# schema_v3_0.net
KiCad netlist of a schematic drawn in EAGLE
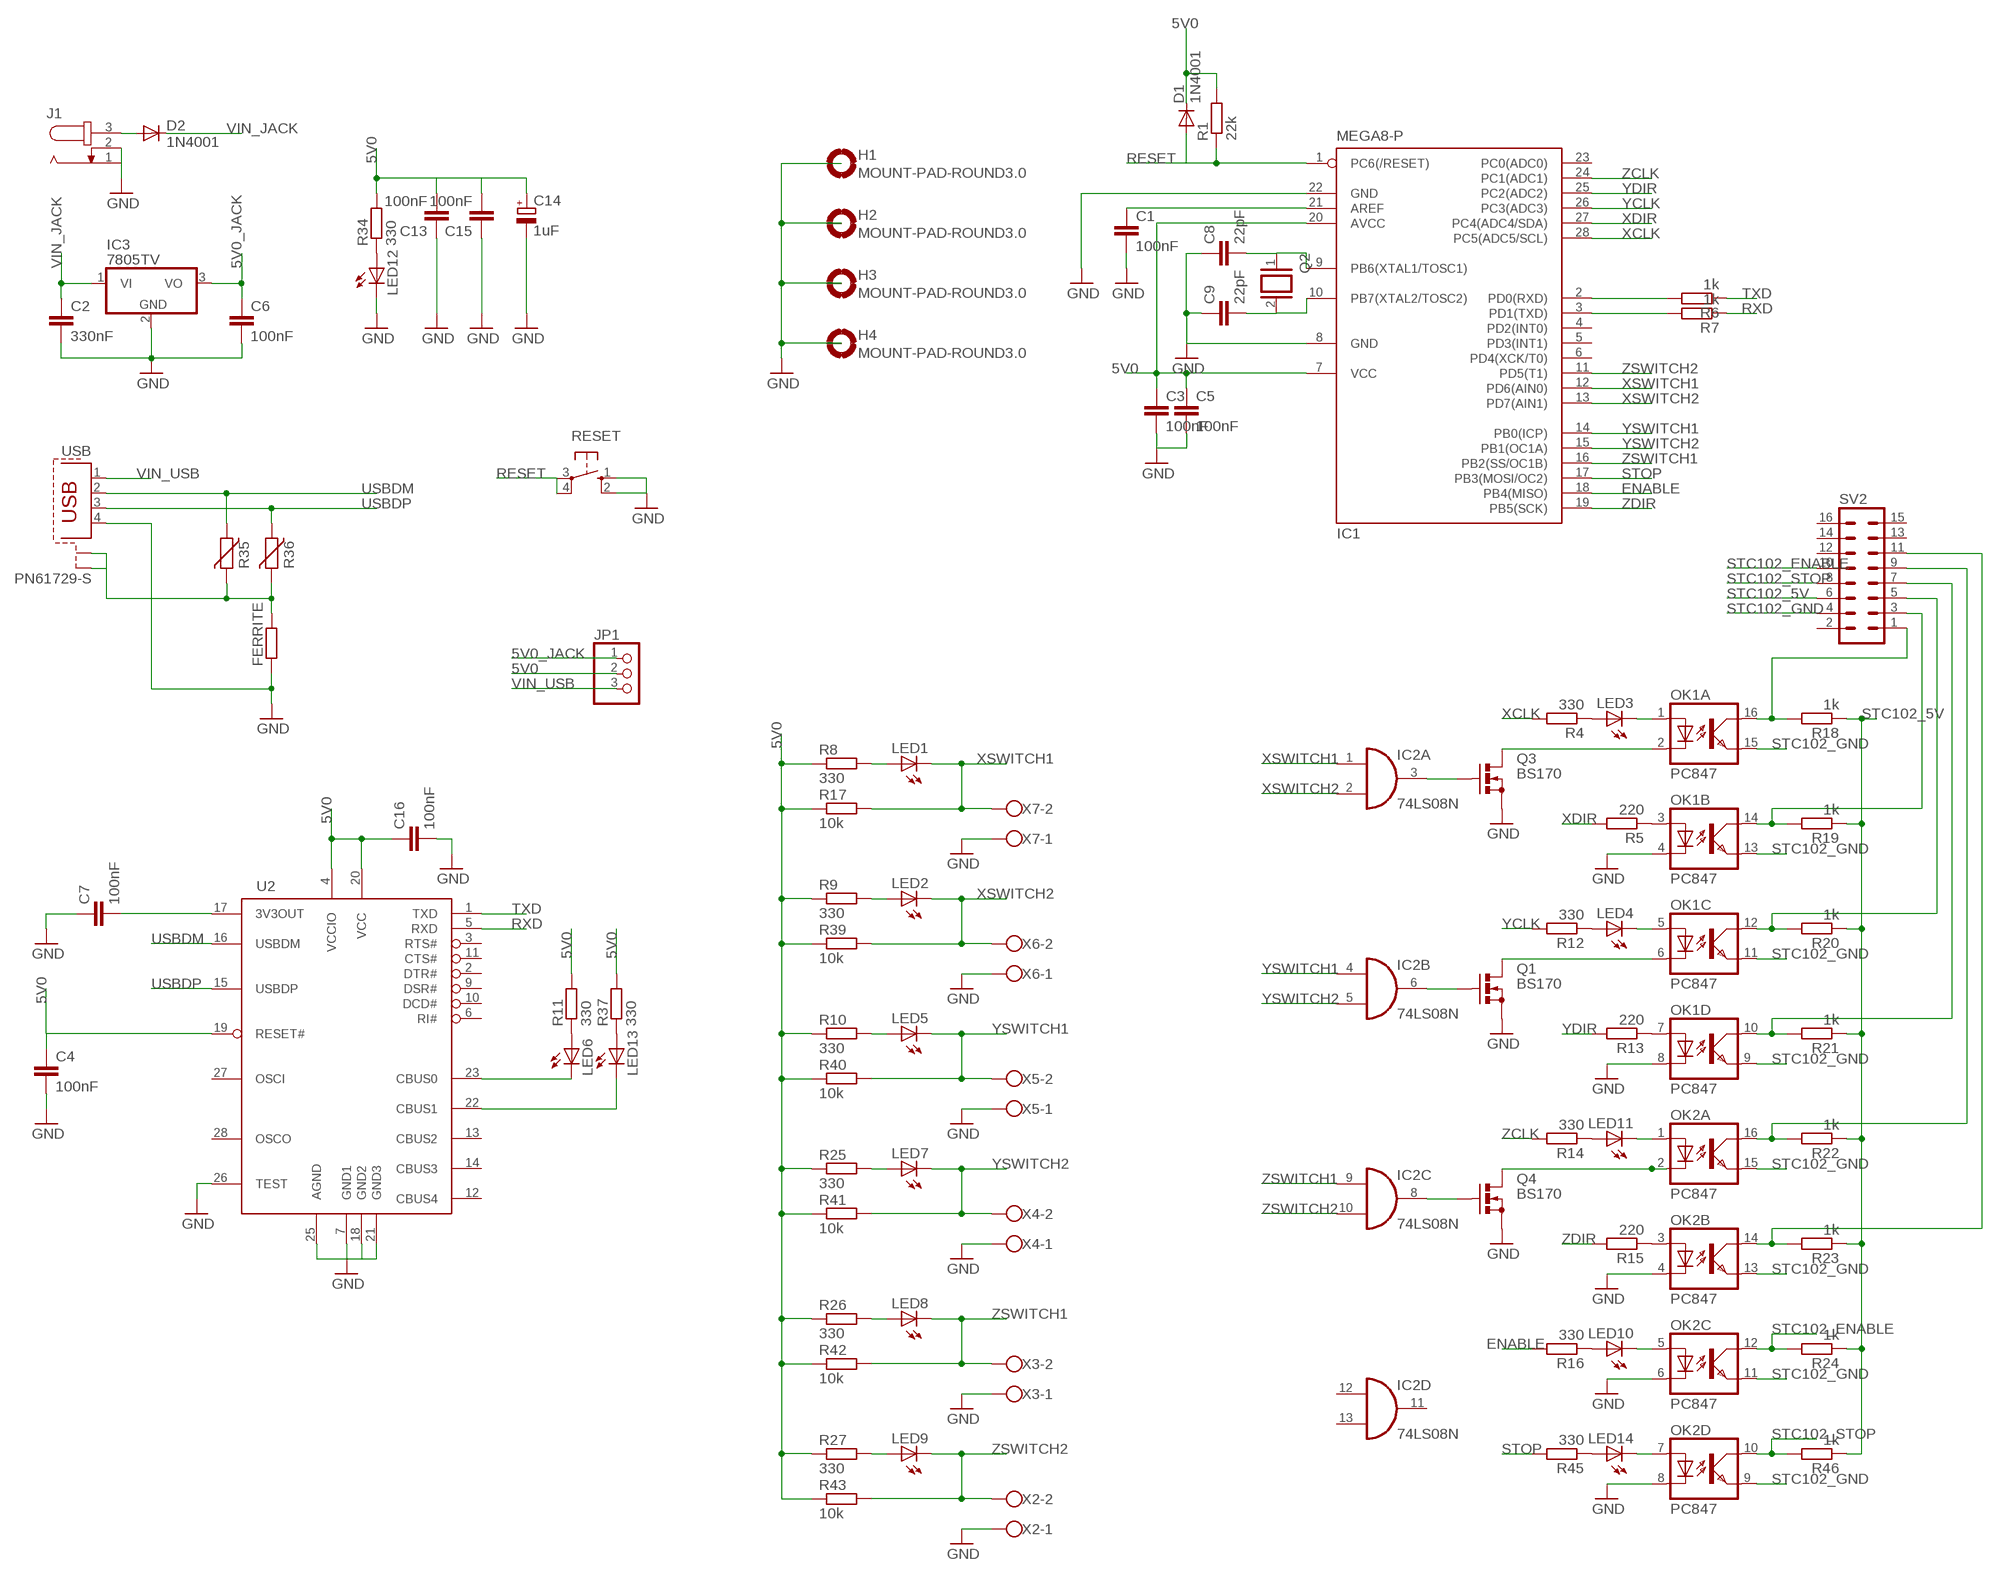
[diagram p0: schematic, sheet 1]

(export (version "E")
  (design (tool "Eeschema 10.0.6"))
  (components
    (comp (ref "C1")
      (value "100nF")
      (footprint "eagle-import:C0805")
      (libsource (lib "eagle-import") (part "C-EUC0805"))
    )
    (comp (ref "C2")
      (value "330nF")
      (footprint "eagle-import:C025-025X050")
      (libsource (lib "eagle-import") (part "C-EU025-025X050"))
    )
    (comp (ref "C3")
      (value "100nF")
      (footprint "eagle-import:C025-025X050")
      (libsource (lib "eagle-import") (part "C-EU025-025X050"))
    )
    (comp (ref "C4")
      (value "100nF")
      (footprint "eagle-import:C0603K")
      (libsource (lib "eagle-import") (part "C-EUC0603K"))
    )
    (comp (ref "C5")
      (value "100nF")
      (footprint "eagle-import:C025-025X050")
      (libsource (lib "eagle-import") (part "C-EU025-025X050"))
    )
    (comp (ref "C6")
      (value "100nF")
      (footprint "eagle-import:C025-025X050")
      (libsource (lib "eagle-import") (part "C-EU025-025X050"))
    )
    (comp (ref "C7")
      (value "100nF")
      (footprint "eagle-import:C0603K")
      (libsource (lib "eagle-import") (part "C-EUC0603K"))
    )
    (comp (ref "C8")
      (value "22pF")
      (footprint "eagle-import:C025-025X050")
      (libsource (lib "eagle-import") (part "C-EU025-025X050"))
    )
    (comp (ref "C9")
      (value "22pF")
      (footprint "eagle-import:C025-025X050")
      (libsource (lib "eagle-import") (part "C-EU025-025X050"))
    )
    (comp (ref "C13")
      (value "100nF")
      (footprint "eagle-import:C025-025X050")
      (libsource (lib "eagle-import") (part "C-EU025-025X050"))
    )
    (comp (ref "C14")
      (value "1uF")
      (footprint "eagle-import:E2,5-5")
      (libsource (lib "eagle-import") (part "CPOL-EUE2.5-5"))
    )
    (comp (ref "C15")
      (value "100nF")
      (footprint "eagle-import:C025-025X050")
      (libsource (lib "eagle-import") (part "C-EU025-025X050"))
    )
    (comp (ref "C16")
      (value "100nF")
      (footprint "eagle-import:C0603K")
      (libsource (lib "eagle-import") (part "C-EUC0603K"))
    )
    (comp (ref "D1")
      (value "1N4001")
      (footprint "eagle-import:DO41-10")
      (libsource (lib "eagle-import") (part "1N4004"))
    )
    (comp (ref "D2")
      (value "1N4001")
      (footprint "eagle-import:DO41-10")
      (libsource (lib "eagle-import") (part "1N4004"))
    )
    (comp (ref "FERRITE")
      (value "R-EU_M0805")
      (footprint "eagle-import:M0805")
      (libsource (lib "eagle-import") (part "resistor_R-EU_M0805"))
    )
    (comp (ref "H1")
      (value "MOUNT-PAD-ROUND3.0")
      (footprint "eagle-import:3,0-PAD")
      (libsource (lib "eagle-import") (part "MOUNT-PAD-ROUND3.0"))
    )
    (comp (ref "H2")
      (value "MOUNT-PAD-ROUND3.0")
      (footprint "eagle-import:3,0-PAD")
      (libsource (lib "eagle-import") (part "MOUNT-PAD-ROUND3.0"))
    )
    (comp (ref "H3")
      (value "MOUNT-PAD-ROUND3.0")
      (footprint "eagle-import:3,0-PAD")
      (libsource (lib "eagle-import") (part "MOUNT-PAD-ROUND3.0"))
    )
    (comp (ref "H4")
      (value "MOUNT-PAD-ROUND3.0")
      (footprint "eagle-import:3,0-PAD")
      (libsource (lib "eagle-import") (part "MOUNT-PAD-ROUND3.0"))
    )
    (comp (ref "IC1")
      (value "MEGA8-P")
      (footprint "eagle-import:DIL28-3")
      (libsource (lib "eagle-import") (part "MEGA8-P"))
    )
    (comp (ref "IC2")
      (value "74LS08N")
      (footprint "eagle-import:DIL14")
      (libsource (lib "eagle-import") (part "7408NLS"))
    )
    (comp (ref "IC3")
      (value "7805TV")
      (footprint "eagle-import:TO220V")
      (libsource (lib "eagle-import") (part "78TV05"))
    )
    (comp (ref "J1")
      (value "JACK-PLUG0")
      (footprint "eagle-import:SPC4077")
      (libsource (lib "eagle-import") (part "JACK-PLUG0"))
    )
    (comp (ref "JP1")
      (value "PINHD-1X3")
      (footprint "eagle-import:1X03")
      (libsource (lib "eagle-import") (part "PINHD-1X3"))
    )
    (comp (ref "LED1")
      (value "LED3MM")
      (footprint "eagle-import:LED3MM")
      (libsource (lib "eagle-import") (part "LED3MM"))
    )
    (comp (ref "LED2")
      (value "LED3MM")
      (footprint "eagle-import:LED3MM")
      (libsource (lib "eagle-import") (part "LED3MM"))
    )
    (comp (ref "LED3")
      (value "LED3MM")
      (footprint "eagle-import:LED3MM")
      (libsource (lib "eagle-import") (part "LED3MM"))
    )
    (comp (ref "LED4")
      (value "LED3MM")
      (footprint "eagle-import:LED3MM")
      (libsource (lib "eagle-import") (part "LED3MM"))
    )
    (comp (ref "LED5")
      (value "LED3MM")
      (footprint "eagle-import:LED3MM")
      (libsource (lib "eagle-import") (part "LED3MM"))
    )
    (comp (ref "LED6")
      (value "LED3MM")
      (footprint "eagle-import:LED3MM")
      (libsource (lib "eagle-import") (part "LED3MM"))
    )
    (comp (ref "LED7")
      (value "LED3MM")
      (footprint "eagle-import:LED3MM")
      (libsource (lib "eagle-import") (part "LED3MM"))
    )
    (comp (ref "LED8")
      (value "LED3MM")
      (footprint "eagle-import:LED3MM")
      (libsource (lib "eagle-import") (part "LED3MM"))
    )
    (comp (ref "LED9")
      (value "LED3MM")
      (footprint "eagle-import:LED3MM")
      (libsource (lib "eagle-import") (part "LED3MM"))
    )
    (comp (ref "LED10")
      (value "LED3MM")
      (footprint "eagle-import:LED3MM")
      (libsource (lib "eagle-import") (part "LED3MM"))
    )
    (comp (ref "LED11")
      (value "LED3MM")
      (footprint "eagle-import:LED3MM")
      (libsource (lib "eagle-import") (part "LED3MM"))
    )
    (comp (ref "LED12")
      (value "LED3MM")
      (footprint "eagle-import:LED3MM")
      (libsource (lib "eagle-import") (part "LED3MM"))
    )
    (comp (ref "LED13")
      (value "LED3MM")
      (footprint "eagle-import:LED3MM")
      (libsource (lib "eagle-import") (part "LED3MM"))
    )
    (comp (ref "LED14")
      (value "LED3MM")
      (footprint "eagle-import:LED3MM")
      (libsource (lib "eagle-import") (part "LED3MM"))
    )
    (comp (ref "OK1")
      (value "PC847")
      (footprint "eagle-import:DIL16")
      (libsource (lib "eagle-import") (part "PC847"))
    )
    (comp (ref "OK2")
      (value "PC847")
      (footprint "eagle-import:DIL16")
      (libsource (lib "eagle-import") (part "PC847"))
    )
    (comp (ref "Q1")
      (value "BS170")
      (footprint "eagle-import:SOT54E")
      (libsource (lib "eagle-import") (part "BS170"))
    )
    (comp (ref "Q2")
      (value "XTAL/S")
      (footprint "eagle-import:QS")
      (libsource (lib "eagle-import") (part "XTAL/S"))
    )
    (comp (ref "Q3")
      (value "BS170")
      (footprint "eagle-import:SOT54E")
      (libsource (lib "eagle-import") (part "BS170"))
    )
    (comp (ref "Q4")
      (value "BS170")
      (footprint "eagle-import:SOT54E")
      (libsource (lib "eagle-import") (part "BS170"))
    )
    (comp (ref "R1")
      (value "22k")
      (footprint "eagle-import:0207_10")
      (libsource (lib "eagle-import") (part "R-EU_0207/10"))
    )
    (comp (ref "R4")
      (value "330")
      (footprint "eagle-import:0207_10")
      (libsource (lib "eagle-import") (part "R-EU_0207/10"))
    )
    (comp (ref "R5")
      (value "220")
      (footprint "eagle-import:0207_10")
      (libsource (lib "eagle-import") (part "R-EU_0207/10"))
    )
    (comp (ref "R6")
      (value "1k")
      (footprint "eagle-import:0207_10")
      (libsource (lib "eagle-import") (part "R-EU_0207/10"))
    )
    (comp (ref "R7")
      (value "1k")
      (footprint "eagle-import:0207_10")
      (libsource (lib "eagle-import") (part "R-EU_0207/10"))
    )
    (comp (ref "R8")
      (value "330")
      (footprint "eagle-import:0207_10")
      (libsource (lib "eagle-import") (part "R-EU_0207/10"))
    )
    (comp (ref "R9")
      (value "330")
      (footprint "eagle-import:0207_10")
      (libsource (lib "eagle-import") (part "R-EU_0207/10"))
    )
    (comp (ref "R10")
      (value "330")
      (footprint "eagle-import:0207_10")
      (libsource (lib "eagle-import") (part "R-EU_0207/10"))
    )
    (comp (ref "R11")
      (value "330")
      (footprint "eagle-import:0207_10")
      (libsource (lib "eagle-import") (part "R-EU_0207/10"))
    )
    (comp (ref "R12")
      (value "330")
      (footprint "eagle-import:0207_10")
      (libsource (lib "eagle-import") (part "R-EU_0207/10"))
    )
    (comp (ref "R13")
      (value "220")
      (footprint "eagle-import:0207_10")
      (libsource (lib "eagle-import") (part "R-EU_0207/10"))
    )
    (comp (ref "R14")
      (value "330")
      (footprint "eagle-import:0207_10")
      (libsource (lib "eagle-import") (part "R-EU_0207/10"))
    )
    (comp (ref "R15")
      (value "220")
      (footprint "eagle-import:0207_10")
      (libsource (lib "eagle-import") (part "R-EU_0207/10"))
    )
    (comp (ref "R16")
      (value "330")
      (footprint "eagle-import:0207_10")
      (libsource (lib "eagle-import") (part "R-EU_0207/10"))
    )
    (comp (ref "R17")
      (value "10k")
      (footprint "eagle-import:0207_10")
      (libsource (lib "eagle-import") (part "R-EU_0207/10"))
    )
    (comp (ref "R18")
      (value "1k")
      (footprint "eagle-import:0207_10")
      (libsource (lib "eagle-import") (part "R-EU_0207/10"))
    )
    (comp (ref "R19")
      (value "1k")
      (footprint "eagle-import:0207_10")
      (libsource (lib "eagle-import") (part "R-EU_0207/10"))
    )
    (comp (ref "R20")
      (value "1k")
      (footprint "eagle-import:0207_10")
      (libsource (lib "eagle-import") (part "R-EU_0207/10"))
    )
    (comp (ref "R21")
      (value "1k")
      (footprint "eagle-import:0207_10")
      (libsource (lib "eagle-import") (part "R-EU_0207/10"))
    )
    (comp (ref "R22")
      (value "1k")
      (footprint "eagle-import:0207_10")
      (libsource (lib "eagle-import") (part "R-EU_0207/10"))
    )
    (comp (ref "R23")
      (value "1k")
      (footprint "eagle-import:0207_10")
      (libsource (lib "eagle-import") (part "R-EU_0207/10"))
    )
    (comp (ref "R24")
      (value "1k")
      (footprint "eagle-import:0207_10")
      (libsource (lib "eagle-import") (part "R-EU_0207/10"))
    )
    (comp (ref "R25")
      (value "330")
      (footprint "eagle-import:0207_10")
      (libsource (lib "eagle-import") (part "R-EU_0207/10"))
    )
    (comp (ref "R26")
      (value "330")
      (footprint "eagle-import:0207_10")
      (libsource (lib "eagle-import") (part "R-EU_0207/10"))
    )
    (comp (ref "R27")
      (value "330")
      (footprint "eagle-import:0207_10")
      (libsource (lib "eagle-import") (part "R-EU_0207/10"))
    )
    (comp (ref "R34")
      (value "330")
      (footprint "eagle-import:0207_10")
      (libsource (lib "eagle-import") (part "R-EU_0207/10"))
    )
    (comp (ref "R35")
      (value "VARISTORCN0603")
      (footprint "eagle-import:CT_CN0603")
      (libsource (lib "eagle-import") (part "VARISTORCN0603"))
    )
    (comp (ref "R36")
      (value "VARISTORCN0603")
      (footprint "eagle-import:CT_CN0603")
      (libsource (lib "eagle-import") (part "VARISTORCN0603"))
    )
    (comp (ref "R37")
      (value "330")
      (footprint "eagle-import:0207_10")
      (libsource (lib "eagle-import") (part "R-EU_0207/10"))
    )
    (comp (ref "R39")
      (value "10k")
      (footprint "eagle-import:0207_10")
      (libsource (lib "eagle-import") (part "R-EU_0207/10"))
    )
    (comp (ref "R40")
      (value "10k")
      (footprint "eagle-import:0207_10")
      (libsource (lib "eagle-import") (part "R-EU_0207/10"))
    )
    (comp (ref "R41")
      (value "10k")
      (footprint "eagle-import:0207_10")
      (libsource (lib "eagle-import") (part "R-EU_0207/10"))
    )
    (comp (ref "R42")
      (value "10k")
      (footprint "eagle-import:0207_10")
      (libsource (lib "eagle-import") (part "R-EU_0207/10"))
    )
    (comp (ref "R43")
      (value "10k")
      (footprint "eagle-import:0207_10")
      (libsource (lib "eagle-import") (part "R-EU_0207/10"))
    )
    (comp (ref "R45")
      (value "330")
      (footprint "eagle-import:0207_10")
      (libsource (lib "eagle-import") (part "R-EU_0207/10"))
    )
    (comp (ref "R46")
      (value "1k")
      (footprint "eagle-import:0207_10")
      (libsource (lib "eagle-import") (part "R-EU_0207/10"))
    )
    (comp (ref "RESET")
      (value "10-XX")
      (footprint "eagle-import:B3F-10XX")
      (fields (field (name "MPN") "B3F-1000"))
      (libsource (lib "eagle-import") (part "10-XX"))
    )
    (comp (ref "SV2")
      (value "MA08-2")
      (footprint "eagle-import:MA08-2")
      (libsource (lib "eagle-import") (part "MA08-2"))
    )
    (comp (ref "U2")
      (value "FT232RL")
      (footprint "eagle-import:SSOP28DB")
      (libsource (lib "eagle-import") (part "FT232RL"))
    )
    (comp (ref "USB")
      (value "PN61729-S")
      (footprint "eagle-import:PN61729-S")
      (fields (field (name "OC_FARNELL") "unknown") (field (name "OC_NEWARK") "unknown"))
      (libsource (lib "eagle-import") (part "PN61729-S"))
    )
    (comp (ref "X2")
      (value "W237-102")
      (footprint "eagle-import:W237-102")
      (fields (field (name "MPN") "237-102"))
      (libsource (lib "eagle-import") (part "W237-102"))
    )
    (comp (ref "X3")
      (value "W237-102")
      (footprint "eagle-import:W237-102")
      (fields (field (name "MPN") "237-102"))
      (libsource (lib "eagle-import") (part "W237-102"))
    )
    (comp (ref "X4")
      (value "W237-102")
      (footprint "eagle-import:W237-102")
      (fields (field (name "MPN") "237-102"))
      (libsource (lib "eagle-import") (part "W237-102"))
    )
    (comp (ref "X5")
      (value "W237-102")
      (footprint "eagle-import:W237-102")
      (fields (field (name "MPN") "237-102"))
      (libsource (lib "eagle-import") (part "W237-102"))
    )
    (comp (ref "X6")
      (value "W237-102")
      (footprint "eagle-import:W237-102")
      (fields (field (name "MPN") "237-102"))
      (libsource (lib "eagle-import") (part "W237-102"))
    )
    (comp (ref "X7")
      (value "W237-102")
      (footprint "eagle-import:W237-102")
      (fields (field (name "MPN") "237-102"))
      (libsource (lib "eagle-import") (part "W237-102"))
    )
  )
  (nets
    (net (code "1") (name "/5V0") (class "Default")
      (node (ref "C13") (pin "2") (pinfunction "2_2") (pintype "passive"))
      (node (ref "C14") (pin "+") (pinfunction "+_+") (pintype "passive"))
      (node (ref "C15") (pin "2") (pinfunction "2_2") (pintype "passive"))
      (node (ref "C16") (pin "1") (pinfunction "1_1") (pintype "passive"))
      (node (ref "C3") (pin "1") (pinfunction "1_1") (pintype "passive"))
      (node (ref "C4") (pin "1") (pinfunction "1_1") (pintype "passive"))
      (node (ref "C5") (pin "1") (pinfunction "1_1") (pintype "passive"))
      (node (ref "D1") (pin "C") (pinfunction "C_C") (pintype "passive"))
      (node (ref "IC1") (pin "20") (pinfunction "AVCC_20") (pintype "power_in"))
      (node (ref "IC1") (pin "7") (pinfunction "VCC_7") (pintype "power_in"))
      (node (ref "JP1") (pin "2") (pinfunction "2_2") (pintype "passive"))
      (node (ref "R1") (pin "2") (pinfunction "2_2") (pintype "passive"))
      (node (ref "R10") (pin "1") (pinfunction "1_1") (pintype "passive"))
      (node (ref "R11") (pin "2") (pinfunction "2_2") (pintype "passive"))
      (node (ref "R17") (pin "1") (pinfunction "1_1") (pintype "passive"))
      (node (ref "R25") (pin "1") (pinfunction "1_1") (pintype "passive"))
      (node (ref "R26") (pin "1") (pinfunction "1_1") (pintype "passive"))
      (node (ref "R27") (pin "1") (pinfunction "1_1") (pintype "passive"))
      (node (ref "R34") (pin "2") (pinfunction "2_2") (pintype "passive"))
      (node (ref "R37") (pin "2") (pinfunction "2_2") (pintype "passive"))
      (node (ref "R39") (pin "1") (pinfunction "1_1") (pintype "passive"))
      (node (ref "R40") (pin "1") (pinfunction "1_1") (pintype "passive"))
      (node (ref "R41") (pin "1") (pinfunction "1_1") (pintype "passive"))
      (node (ref "R42") (pin "1") (pinfunction "1_1") (pintype "passive"))
      (node (ref "R43") (pin "1") (pinfunction "1_1") (pintype "passive"))
      (node (ref "R8") (pin "1") (pinfunction "1_1") (pintype "passive"))
      (node (ref "R9") (pin "1") (pinfunction "1_1") (pintype "passive"))
      (node (ref "U2") (pin "19") (pinfunction "RESET#_19") (pintype "input"))
      (node (ref "U2") (pin "20") (pinfunction "VCC_20") (pintype "power_in"))
      (node (ref "U2") (pin "4") (pinfunction "VCCIO_4") (pintype "power_in"))
    )
    (net (code "2") (name "/5V0_JACK") (class "Default")
      (node (ref "C6") (pin "1") (pinfunction "1_1") (pintype "passive"))
      (node (ref "IC3") (pin "3") (pinfunction "VO_3") (pintype "passive"))
      (node (ref "JP1") (pin "1") (pinfunction "1_1") (pintype "passive"))
    )
    (net (code "3") (name "/ENABLE") (class "Default")
      (node (ref "IC1") (pin "18") (pinfunction "PB4(MISO)_18") (pintype "bidirectional"))
      (node (ref "R16") (pin "2") (pinfunction "2_2") (pintype "passive"))
    )
    (net (code "4") (name "/RESET") (class "Default")
      (node (ref "D1") (pin "A") (pinfunction "A_A") (pintype "passive"))
      (node (ref "IC1") (pin "1") (pinfunction "PC6(/RESET)_1") (pintype "bidirectional"))
      (node (ref "R1") (pin "1") (pinfunction "1_1") (pintype "passive"))
      (node (ref "RESET") (pin "3") (pinfunction "P_3") (pintype "passive"))
      (node (ref "RESET") (pin "4") (pinfunction "P1_4") (pintype "passive"))
    )
    (net (code "5") (name "/RXD") (class "Default")
      (node (ref "R7") (pin "1") (pinfunction "1_1") (pintype "passive"))
      (node (ref "U2") (pin "5") (pinfunction "RXD_5") (pintype "input"))
    )
    (net (code "6") (name "/STC102_5V") (class "Default")
      (node (ref "R18") (pin "1") (pinfunction "1_1") (pintype "passive"))
      (node (ref "R19") (pin "1") (pinfunction "1_1") (pintype "passive"))
      (node (ref "R20") (pin "1") (pinfunction "1_1") (pintype "passive"))
      (node (ref "R21") (pin "1") (pinfunction "1_1") (pintype "passive"))
      (node (ref "R22") (pin "1") (pinfunction "1_1") (pintype "passive"))
      (node (ref "R23") (pin "1") (pinfunction "1_1") (pintype "passive"))
      (node (ref "R24") (pin "1") (pinfunction "1_1") (pintype "passive"))
      (node (ref "R46") (pin "1") (pinfunction "1_1") (pintype "passive"))
      (node (ref "SV2") (pin "6") (pinfunction "6_6") (pintype "passive"))
    )
    (net (code "7") (name "/STC102_ENABLE") (class "Default")
      (node (ref "OK2") (pin "12") (pinfunction "COL_12") (pintype "passive"))
      (node (ref "R24") (pin "2") (pinfunction "2_2") (pintype "passive"))
      (node (ref "SV2") (pin "10") (pinfunction "10_10") (pintype "passive"))
    )
    (net (code "8") (name "/STC102_GND") (class "Default")
      (node (ref "OK1") (pin "11") (pinfunction "EMIT_11") (pintype "passive"))
      (node (ref "OK1") (pin "13") (pinfunction "EMIT_13") (pintype "passive"))
      (node (ref "OK1") (pin "15") (pinfunction "EMIT_15") (pintype "passive"))
      (node (ref "OK1") (pin "9") (pinfunction "EMIT_9") (pintype "passive"))
      (node (ref "OK2") (pin "11") (pinfunction "EMIT_11") (pintype "passive"))
      (node (ref "OK2") (pin "13") (pinfunction "EMIT_13") (pintype "passive"))
      (node (ref "OK2") (pin "15") (pinfunction "EMIT_15") (pintype "passive"))
      (node (ref "OK2") (pin "9") (pinfunction "EMIT_9") (pintype "passive"))
      (node (ref "SV2") (pin "4") (pinfunction "4_4") (pintype "passive"))
    )
    (net (code "9") (name "/STC102_STOP") (class "Default")
      (node (ref "OK2") (pin "10") (pinfunction "COL_10") (pintype "passive"))
      (node (ref "R46") (pin "2") (pinfunction "2_2") (pintype "passive"))
      (node (ref "SV2") (pin "8") (pinfunction "8_8") (pintype "passive"))
    )
    (net (code "10") (name "/STOP") (class "Default")
      (node (ref "IC1") (pin "17") (pinfunction "PB3(MOSI/OC2)_17") (pintype "bidirectional"))
      (node (ref "R45") (pin "2") (pinfunction "2_2") (pintype "passive"))
    )
    (net (code "11") (name "/TXD") (class "Default")
      (node (ref "R6") (pin "1") (pinfunction "1_1") (pintype "passive"))
      (node (ref "U2") (pin "1") (pinfunction "TXD_1") (pintype "output"))
    )
    (net (code "12") (name "/USBDM") (class "Default")
      (node (ref "R35") (pin "1") (pinfunction "1_1") (pintype "passive"))
      (node (ref "U2") (pin "16") (pinfunction "USBDM_16") (pintype "bidirectional"))
      (node (ref "USB") (pin "2") (pinfunction "2_2") (pintype "passive"))
    )
    (net (code "13") (name "/USBDP") (class "Default")
      (node (ref "R36") (pin "1") (pinfunction "1_1") (pintype "passive"))
      (node (ref "U2") (pin "15") (pinfunction "USBDP_15") (pintype "bidirectional"))
      (node (ref "USB") (pin "3") (pinfunction "3_3") (pintype "passive"))
    )
    (net (code "14") (name "/VIN_JACK") (class "Default")
      (node (ref "C2") (pin "1") (pinfunction "1_1") (pintype "passive"))
      (node (ref "D2") (pin "C") (pinfunction "C_C") (pintype "passive"))
      (node (ref "IC3") (pin "1") (pinfunction "VI_1") (pintype "input"))
    )
    (net (code "15") (name "/VIN_USB") (class "Default")
      (node (ref "JP1") (pin "3") (pinfunction "3_3") (pintype "passive"))
      (node (ref "USB") (pin "1") (pinfunction "1_1") (pintype "passive"))
    )
    (net (code "16") (name "/XCLK") (class "Default")
      (node (ref "IC1") (pin "28") (pinfunction "PC5(ADC5/SCL)_28") (pintype "bidirectional"))
      (node (ref "R4") (pin "2") (pinfunction "2_2") (pintype "passive"))
    )
    (net (code "17") (name "/XDIR") (class "Default")
      (node (ref "IC1") (pin "27") (pinfunction "PC4(ADC4/SDA)_27") (pintype "bidirectional"))
      (node (ref "R5") (pin "2") (pinfunction "2_2") (pintype "passive"))
    )
    (net (code "18") (name "/XSWITCH1") (class "Default")
      (node (ref "IC1") (pin "12") (pinfunction "PD6(AIN0)_12") (pintype "bidirectional"))
      (node (ref "IC2") (pin "1") (pinfunction "I0_1") (pintype "input"))
      (node (ref "LED1") (pin "K") (pinfunction "C_K") (pintype "passive"))
      (node (ref "R17") (pin "2") (pinfunction "2_2") (pintype "passive"))
      (node (ref "X7") (pin "2") (pinfunction "KL_2") (pintype "passive"))
    )
    (net (code "19") (name "/XSWITCH2") (class "Default")
      (node (ref "IC1") (pin "13") (pinfunction "PD7(AIN1)_13") (pintype "bidirectional"))
      (node (ref "IC2") (pin "2") (pinfunction "I1_2") (pintype "input"))
      (node (ref "LED2") (pin "K") (pinfunction "C_K") (pintype "passive"))
      (node (ref "R39") (pin "2") (pinfunction "2_2") (pintype "passive"))
      (node (ref "X6") (pin "2") (pinfunction "KL_2") (pintype "passive"))
    )
    (net (code "20") (name "/YCLK") (class "Default")
      (node (ref "IC1") (pin "26") (pinfunction "PC3(ADC3)_26") (pintype "bidirectional"))
      (node (ref "R12") (pin "2") (pinfunction "2_2") (pintype "passive"))
    )
    (net (code "21") (name "/YDIR") (class "Default")
      (node (ref "IC1") (pin "25") (pinfunction "PC2(ADC2)_25") (pintype "bidirectional"))
      (node (ref "R13") (pin "2") (pinfunction "2_2") (pintype "passive"))
    )
    (net (code "22") (name "/YSWITCH1") (class "Default")
      (node (ref "IC1") (pin "14") (pinfunction "PB0(ICP)_14") (pintype "bidirectional"))
      (node (ref "IC2") (pin "4") (pinfunction "I0_4") (pintype "input"))
      (node (ref "LED5") (pin "K") (pinfunction "C_K") (pintype "passive"))
      (node (ref "R40") (pin "2") (pinfunction "2_2") (pintype "passive"))
      (node (ref "X5") (pin "2") (pinfunction "KL_2") (pintype "passive"))
    )
    (net (code "23") (name "/YSWITCH2") (class "Default")
      (node (ref "IC1") (pin "15") (pinfunction "PB1(OC1A)_15") (pintype "bidirectional"))
      (node (ref "IC2") (pin "5") (pinfunction "I1_5") (pintype "input"))
      (node (ref "LED7") (pin "K") (pinfunction "C_K") (pintype "passive"))
      (node (ref "R41") (pin "2") (pinfunction "2_2") (pintype "passive"))
      (node (ref "X4") (pin "2") (pinfunction "KL_2") (pintype "passive"))
    )
    (net (code "24") (name "/ZCLK") (class "Default")
      (node (ref "IC1") (pin "24") (pinfunction "PC1(ADC1)_24") (pintype "bidirectional"))
      (node (ref "R14") (pin "2") (pinfunction "2_2") (pintype "passive"))
    )
    (net (code "25") (name "/ZDIR") (class "Default")
      (node (ref "IC1") (pin "19") (pinfunction "PB5(SCK)_19") (pintype "bidirectional"))
      (node (ref "R15") (pin "2") (pinfunction "2_2") (pintype "passive"))
    )
    (net (code "26") (name "/ZSWITCH1") (class "Default")
      (node (ref "IC1") (pin "16") (pinfunction "PB2(SS/OC1B)_16") (pintype "bidirectional"))
      (node (ref "IC2") (pin "9") (pinfunction "I0_9") (pintype "input"))
      (node (ref "LED8") (pin "K") (pinfunction "C_K") (pintype "passive"))
      (node (ref "R42") (pin "2") (pinfunction "2_2") (pintype "passive"))
      (node (ref "X3") (pin "2") (pinfunction "KL_2") (pintype "passive"))
    )
    (net (code "27") (name "/ZSWITCH2") (class "Default")
      (node (ref "IC1") (pin "11") (pinfunction "PD5(T1)_11") (pintype "bidirectional"))
      (node (ref "IC2") (pin "10") (pinfunction "I1_10") (pintype "input"))
      (node (ref "LED9") (pin "K") (pinfunction "C_K") (pintype "passive"))
      (node (ref "R43") (pin "2") (pinfunction "2_2") (pintype "passive"))
      (node (ref "X2") (pin "2") (pinfunction "KL_2") (pintype "passive"))
    )
    (net (code "28") (name "GND") (class "Default")
      (node (ref "C1") (pin "2") (pinfunction "2_2") (pintype "passive"))
      (node (ref "C13") (pin "1") (pinfunction "1_1") (pintype "passive"))
      (node (ref "C14") (pin "-") (pinfunction "-_-") (pintype "passive"))
      (node (ref "C15") (pin "1") (pinfunction "1_1") (pintype "passive"))
      (node (ref "C16") (pin "2") (pinfunction "2_2") (pintype "passive"))
      (node (ref "C2") (pin "2") (pinfunction "2_2") (pintype "passive"))
      (node (ref "C3") (pin "2") (pinfunction "2_2") (pintype "passive"))
      (node (ref "C4") (pin "2") (pinfunction "2_2") (pintype "passive"))
      (node (ref "C5") (pin "2") (pinfunction "2_2") (pintype "passive"))
      (node (ref "C6") (pin "2") (pinfunction "2_2") (pintype "passive"))
      (node (ref "C7") (pin "1") (pinfunction "1_1") (pintype "passive"))
      (node (ref "C8") (pin "1") (pinfunction "1_1") (pintype "passive"))
      (node (ref "C9") (pin "1") (pinfunction "1_1") (pintype "passive"))
      (node (ref "FERRITE") (pin "1") (pinfunction "1_1") (pintype "passive"))
      (node (ref "IC1") (pin "22") (pinfunction "GND_22") (pintype "power_in"))
      (node (ref "IC1") (pin "8") (pinfunction "GND_8") (pintype "power_in"))
      (node (ref "IC3") (pin "2") (pinfunction "GND_2") (pintype "passive"))
      (node (ref "J1") (pin "1") (pinfunction "1_1") (pintype "passive"))
      (node (ref "J1") (pin "2") (pinfunction "2_2") (pintype "passive"))
      (node (ref "LED12") (pin "K") (pinfunction "C_K") (pintype "passive"))
      (node (ref "OK1") (pin "4") (pinfunction "C_4") (pintype "passive"))
      (node (ref "OK1") (pin "8") (pinfunction "C_8") (pintype "passive"))
      (node (ref "OK2") (pin "4") (pinfunction "C_4") (pintype "passive"))
      (node (ref "OK2") (pin "6") (pinfunction "C_6") (pintype "passive"))
      (node (ref "OK2") (pin "8") (pinfunction "C_8") (pintype "passive"))
      (node (ref "Q1") (pin "S") (pinfunction "S_S") (pintype "passive"))
      (node (ref "Q3") (pin "S") (pinfunction "S_S") (pintype "passive"))
      (node (ref "Q4") (pin "S") (pinfunction "S_S") (pintype "passive"))
      (node (ref "RESET") (pin "1") (pinfunction "S_1") (pintype "passive"))
      (node (ref "RESET") (pin "2") (pinfunction "S1_2") (pintype "passive"))
      (node (ref "U2") (pin "18") (pinfunction "GND2_18") (pintype "power_in"))
      (node (ref "U2") (pin "21") (pinfunction "GND3_21") (pintype "power_in"))
      (node (ref "U2") (pin "25") (pinfunction "AGND_25") (pintype "power_in"))
      (node (ref "U2") (pin "26") (pinfunction "TEST_26") (pintype "input"))
      (node (ref "U2") (pin "7") (pinfunction "GND1_7") (pintype "power_in"))
      (node (ref "USB") (pin "4") (pinfunction "4_4") (pintype "passive"))
      (node (ref "X2") (pin "1") (pinfunction "KL_1") (pintype "passive"))
      (node (ref "X3") (pin "1") (pinfunction "KL_1") (pintype "passive"))
      (node (ref "X4") (pin "1") (pinfunction "KL_1") (pintype "passive"))
      (node (ref "X5") (pin "1") (pinfunction "KL_1") (pintype "passive"))
      (node (ref "X6") (pin "1") (pinfunction "KL_1") (pintype "passive"))
      (node (ref "X7") (pin "1") (pinfunction "KL_1") (pintype "passive"))
    )
    (net (code "29") (name "Net-(D2-PadA)") (class "Default")
      (node (ref "D2") (pin "A") (pinfunction "A_A") (pintype "passive"))
      (node (ref "J1") (pin "3") (pinfunction "3_3") (pintype "passive"))
    )
    (net (code "30") (name "Net-(FERRITE-Pad2)") (class "Default")
      (node (ref "FERRITE") (pin "2") (pinfunction "2_2") (pintype "passive"))
      (node (ref "R35") (pin "2") (pinfunction "2_2") (pintype "passive"))
      (node (ref "R36") (pin "2") (pinfunction "2_2") (pintype "passive"))
      (node (ref "USB") (pin "S1") (pinfunction "S1_S1") (pintype "passive"))
      (node (ref "USB") (pin "S2") (pinfunction "S2_S2") (pintype "passive"))
    )
    (net (code "31") (name "Net-(IC1-AREF)") (class "Default")
      (node (ref "C1") (pin "1") (pinfunction "1_1") (pintype "passive"))
      (node (ref "IC1") (pin "21") (pinfunction "AREF_21") (pintype "passive"))
    )
    (net (code "32") (name "Net-(IC1-PB6(XTAL1{slash}TOSC1))") (class "Default")
      (node (ref "C8") (pin "2") (pinfunction "2_2") (pintype "passive"))
      (node (ref "IC1") (pin "9") (pinfunction "PB6(XTAL1/TOSC1)_9") (pintype "bidirectional"))
      (node (ref "Q2") (pin "1") (pinfunction "1_1") (pintype "passive"))
    )
    (net (code "33") (name "Net-(IC1-PB7(XTAL2{slash}TOSC2))") (class "Default")
      (node (ref "C9") (pin "2") (pinfunction "2_2") (pintype "passive"))
      (node (ref "IC1") (pin "10") (pinfunction "PB7(XTAL2/TOSC2)_10") (pintype "bidirectional"))
      (node (ref "Q2") (pin "2") (pinfunction "2_2") (pintype "passive"))
    )
    (net (code "34") (name "Net-(IC1-PD0(RXD))") (class "Default")
      (node (ref "IC1") (pin "2") (pinfunction "PD0(RXD)_2") (pintype "bidirectional"))
      (node (ref "R6") (pin "2") (pinfunction "2_2") (pintype "passive"))
    )
    (net (code "35") (name "Net-(IC1-PD1(TXD))") (class "Default")
      (node (ref "IC1") (pin "3") (pinfunction "PD1(TXD)_3") (pintype "bidirectional"))
      (node (ref "R7") (pin "2") (pinfunction "2_2") (pintype "passive"))
    )
    (net (code "36") (name "Net-(IC2A-O)") (class "Default")
      (node (ref "IC2") (pin "3") (pinfunction "O_3") (pintype "output"))
      (node (ref "Q3") (pin "G") (pinfunction "G_G") (pintype "passive"))
    )
    (net (code "37") (name "Net-(IC2B-O)") (class "Default")
      (node (ref "IC2") (pin "6") (pinfunction "O_6") (pintype "output"))
      (node (ref "Q1") (pin "G") (pinfunction "G_G") (pintype "passive"))
    )
    (net (code "38") (name "Net-(IC2C-O)") (class "Default")
      (node (ref "IC2") (pin "8") (pinfunction "O_8") (pintype "output"))
      (node (ref "Q4") (pin "G") (pinfunction "G_G") (pintype "passive"))
    )
    (net (code "39") (name "Net-(LED1-PadA)") (class "Default")
      (node (ref "LED1") (pin "A") (pinfunction "A_A") (pintype "passive"))
      (node (ref "R8") (pin "2") (pinfunction "2_2") (pintype "passive"))
    )
    (net (code "40") (name "Net-(LED2-PadA)") (class "Default")
      (node (ref "LED2") (pin "A") (pinfunction "A_A") (pintype "passive"))
      (node (ref "R9") (pin "2") (pinfunction "2_2") (pintype "passive"))
    )
    (net (code "41") (name "Net-(LED3-C)") (class "Default")
      (node (ref "LED3") (pin "K") (pinfunction "C_K") (pintype "passive"))
      (node (ref "OK1") (pin "1") (pinfunction "A_1") (pintype "passive"))
    )
    (net (code "42") (name "Net-(LED3-PadA)") (class "Default")
      (node (ref "LED3") (pin "A") (pinfunction "A_A") (pintype "passive"))
      (node (ref "R4") (pin "1") (pinfunction "1_1") (pintype "passive"))
    )
    (net (code "43") (name "Net-(LED4-C)") (class "Default")
      (node (ref "LED4") (pin "K") (pinfunction "C_K") (pintype "passive"))
      (node (ref "OK1") (pin "5") (pinfunction "A_5") (pintype "passive"))
    )
    (net (code "44") (name "Net-(LED4-PadA)") (class "Default")
      (node (ref "LED4") (pin "A") (pinfunction "A_A") (pintype "passive"))
      (node (ref "R12") (pin "1") (pinfunction "1_1") (pintype "passive"))
    )
    (net (code "45") (name "Net-(LED5-PadA)") (class "Default")
      (node (ref "LED5") (pin "A") (pinfunction "A_A") (pintype "passive"))
      (node (ref "R10") (pin "2") (pinfunction "2_2") (pintype "passive"))
    )
    (net (code "46") (name "Net-(LED6-C)") (class "Default")
      (node (ref "LED6") (pin "K") (pinfunction "C_K") (pintype "passive"))
      (node (ref "U2") (pin "23") (pinfunction "CBUS0_23") (pintype "bidirectional"))
    )
    (net (code "47") (name "Net-(LED6-PadA)") (class "Default")
      (node (ref "LED6") (pin "A") (pinfunction "A_A") (pintype "passive"))
      (node (ref "R11") (pin "1") (pinfunction "1_1") (pintype "passive"))
    )
    (net (code "48") (name "Net-(LED7-PadA)") (class "Default")
      (node (ref "LED7") (pin "A") (pinfunction "A_A") (pintype "passive"))
      (node (ref "R25") (pin "2") (pinfunction "2_2") (pintype "passive"))
    )
    (net (code "49") (name "Net-(LED8-PadA)") (class "Default")
      (node (ref "LED8") (pin "A") (pinfunction "A_A") (pintype "passive"))
      (node (ref "R26") (pin "2") (pinfunction "2_2") (pintype "passive"))
    )
    (net (code "50") (name "Net-(LED9-PadA)") (class "Default")
      (node (ref "LED9") (pin "A") (pinfunction "A_A") (pintype "passive"))
      (node (ref "R27") (pin "2") (pinfunction "2_2") (pintype "passive"))
    )
    (net (code "51") (name "Net-(LED10-C)") (class "Default")
      (node (ref "LED10") (pin "K") (pinfunction "C_K") (pintype "passive"))
      (node (ref "OK2") (pin "5") (pinfunction "A_5") (pintype "passive"))
    )
    (net (code "52") (name "Net-(LED10-PadA)") (class "Default")
      (node (ref "LED10") (pin "A") (pinfunction "A_A") (pintype "passive"))
      (node (ref "R16") (pin "1") (pinfunction "1_1") (pintype "passive"))
    )
    (net (code "53") (name "Net-(LED11-C)") (class "Default")
      (node (ref "LED11") (pin "K") (pinfunction "C_K") (pintype "passive"))
      (node (ref "OK2") (pin "1") (pinfunction "A_1") (pintype "passive"))
    )
    (net (code "54") (name "Net-(LED11-PadA)") (class "Default")
      (node (ref "LED11") (pin "A") (pinfunction "A_A") (pintype "passive"))
      (node (ref "R14") (pin "1") (pinfunction "1_1") (pintype "passive"))
    )
    (net (code "55") (name "Net-(LED12-PadA)") (class "Default")
      (node (ref "LED12") (pin "A") (pinfunction "A_A") (pintype "passive"))
      (node (ref "R34") (pin "1") (pinfunction "1_1") (pintype "passive"))
    )
    (net (code "56") (name "Net-(LED13-C)") (class "Default")
      (node (ref "LED13") (pin "K") (pinfunction "C_K") (pintype "passive"))
      (node (ref "U2") (pin "22") (pinfunction "CBUS1_22") (pintype "bidirectional"))
    )
    (net (code "57") (name "Net-(LED13-PadA)") (class "Default")
      (node (ref "LED13") (pin "A") (pinfunction "A_A") (pintype "passive"))
      (node (ref "R37") (pin "1") (pinfunction "1_1") (pintype "passive"))
    )
    (net (code "58") (name "Net-(LED14-C)") (class "Default")
      (node (ref "LED14") (pin "K") (pinfunction "C_K") (pintype "passive"))
      (node (ref "OK2") (pin "7") (pinfunction "A_7") (pintype "passive"))
    )
    (net (code "59") (name "Net-(LED14-PadA)") (class "Default")
      (node (ref "LED14") (pin "A") (pinfunction "A_A") (pintype "passive"))
      (node (ref "R45") (pin "1") (pinfunction "1_1") (pintype "passive"))
    )
    (net (code "60") (name "Net-(OK1A-C)") (class "Default")
      (node (ref "OK1") (pin "2") (pinfunction "C_2") (pintype "passive"))
      (node (ref "Q3") (pin "D") (pinfunction "D_D") (pintype "passive"))
    )
    (net (code "61") (name "Net-(OK1A-COL)") (class "Default")
      (node (ref "OK1") (pin "16") (pinfunction "COL_16") (pintype "passive"))
      (node (ref "R18") (pin "2") (pinfunction "2_2") (pintype "passive"))
      (node (ref "SV2") (pin "1") (pinfunction "1_1") (pintype "passive"))
    )
    (net (code "62") (name "Net-(OK1B-A)") (class "Default")
      (node (ref "OK1") (pin "3") (pinfunction "A_3") (pintype "passive"))
      (node (ref "R5") (pin "1") (pinfunction "1_1") (pintype "passive"))
    )
    (net (code "63") (name "Net-(OK1B-COL)") (class "Default")
      (node (ref "OK1") (pin "14") (pinfunction "COL_14") (pintype "passive"))
      (node (ref "R19") (pin "2") (pinfunction "2_2") (pintype "passive"))
      (node (ref "SV2") (pin "3") (pinfunction "3_3") (pintype "passive"))
    )
    (net (code "64") (name "Net-(OK1C-C)") (class "Default")
      (node (ref "OK1") (pin "6") (pinfunction "C_6") (pintype "passive"))
      (node (ref "Q1") (pin "D") (pinfunction "D_D") (pintype "passive"))
    )
    (net (code "65") (name "Net-(OK1C-COL)") (class "Default")
      (node (ref "OK1") (pin "12") (pinfunction "COL_12") (pintype "passive"))
      (node (ref "R20") (pin "2") (pinfunction "2_2") (pintype "passive"))
      (node (ref "SV2") (pin "5") (pinfunction "5_5") (pintype "passive"))
    )
    (net (code "66") (name "Net-(OK1D-A)") (class "Default")
      (node (ref "OK1") (pin "7") (pinfunction "A_7") (pintype "passive"))
      (node (ref "R13") (pin "1") (pinfunction "1_1") (pintype "passive"))
    )
    (net (code "67") (name "Net-(OK1D-COL)") (class "Default")
      (node (ref "OK1") (pin "10") (pinfunction "COL_10") (pintype "passive"))
      (node (ref "R21") (pin "2") (pinfunction "2_2") (pintype "passive"))
      (node (ref "SV2") (pin "7") (pinfunction "7_7") (pintype "passive"))
    )
    (net (code "68") (name "Net-(OK2A-C)") (class "Default")
      (node (ref "OK2") (pin "2") (pinfunction "C_2") (pintype "passive"))
      (node (ref "Q4") (pin "D") (pinfunction "D_D") (pintype "passive"))
    )
    (net (code "69") (name "Net-(OK2A-COL)") (class "Default")
      (node (ref "OK2") (pin "16") (pinfunction "COL_16") (pintype "passive"))
      (node (ref "R22") (pin "2") (pinfunction "2_2") (pintype "passive"))
      (node (ref "SV2") (pin "9") (pinfunction "9_9") (pintype "passive"))
    )
    (net (code "70") (name "Net-(OK2B-A)") (class "Default")
      (node (ref "OK2") (pin "3") (pinfunction "A_3") (pintype "passive"))
      (node (ref "R15") (pin "1") (pinfunction "1_1") (pintype "passive"))
    )
    (net (code "71") (name "Net-(OK2B-COL)") (class "Default")
      (node (ref "OK2") (pin "14") (pinfunction "COL_14") (pintype "passive"))
      (node (ref "R23") (pin "2") (pinfunction "2_2") (pintype "passive"))
      (node (ref "SV2") (pin "11") (pinfunction "11_11") (pintype "passive"))
    )
    (net (code "72") (name "Net-(U2-3V3OUT)") (class "Default")
      (node (ref "C7") (pin "2") (pinfunction "2_2") (pintype "passive"))
      (node (ref "U2") (pin "17") (pinfunction "3V3OUT_17") (pintype "output"))
    )
    (net (code "73") (name "unconnected-(H1-MOUNT-PadB3,0)") (class "Default")
      (node (ref "H1") (pin "B3,0") (pinfunction "MOUNT_B3,0") (pintype "passive"))
    )
    (net (code "74") (name "unconnected-(H2-MOUNT-PadB3,0)") (class "Default")
      (node (ref "H2") (pin "B3,0") (pinfunction "MOUNT_B3,0") (pintype "passive"))
    )
    (net (code "75") (name "unconnected-(H3-MOUNT-PadB3,0)") (class "Default")
      (node (ref "H3") (pin "B3,0") (pinfunction "MOUNT_B3,0") (pintype "passive"))
    )
    (net (code "76") (name "unconnected-(H4-MOUNT-PadB3,0)") (class "Default")
      (node (ref "H4") (pin "B3,0") (pinfunction "MOUNT_B3,0") (pintype "passive"))
    )
    (net (code "77") (name "unconnected-(IC1-PC0(ADC0)-Pad23)") (class "Default")
      (node (ref "IC1") (pin "23") (pinfunction "PC0(ADC0)_23") (pintype "bidirectional"))
    )
    (net (code "78") (name "unconnected-(IC1-PD2(INT0)-Pad4)") (class "Default")
      (node (ref "IC1") (pin "4") (pinfunction "PD2(INT0)_4") (pintype "bidirectional"))
    )
    (net (code "79") (name "unconnected-(IC1-PD3(INT1)-Pad5)") (class "Default")
      (node (ref "IC1") (pin "5") (pinfunction "PD3(INT1)_5") (pintype "bidirectional"))
    )
    (net (code "80") (name "unconnected-(IC1-PD4(XCK{slash}T0)-Pad6)") (class "Default")
      (node (ref "IC1") (pin "6") (pinfunction "PD4(XCK/T0)_6") (pintype "bidirectional"))
    )
    (net (code "81") (name "unconnected-(IC2D-I0-Pad12)") (class "Default")
      (node (ref "IC2") (pin "12") (pinfunction "I0_12") (pintype "input"))
    )
    (net (code "82") (name "unconnected-(IC2D-I1-Pad13)") (class "Default")
      (node (ref "IC2") (pin "13") (pinfunction "I1_13") (pintype "input"))
    )
    (net (code "83") (name "unconnected-(IC2D-O-Pad11)") (class "Default")
      (node (ref "IC2") (pin "11") (pinfunction "O_11") (pintype "output"))
    )
    (net (code "84") (name "unconnected-(SV2-Pad2)") (class "Default")
      (node (ref "SV2") (pin "2") (pinfunction "2_2") (pintype "passive"))
    )
    (net (code "85") (name "unconnected-(SV2-Pad12)") (class "Default")
      (node (ref "SV2") (pin "12") (pinfunction "12_12") (pintype "passive"))
    )
    (net (code "86") (name "unconnected-(SV2-Pad13)") (class "Default")
      (node (ref "SV2") (pin "13") (pinfunction "13_13") (pintype "passive"))
    )
    (net (code "87") (name "unconnected-(SV2-Pad14)") (class "Default")
      (node (ref "SV2") (pin "14") (pinfunction "14_14") (pintype "passive"))
    )
    (net (code "88") (name "unconnected-(SV2-Pad15)") (class "Default")
      (node (ref "SV2") (pin "15") (pinfunction "15_15") (pintype "passive"))
    )
    (net (code "89") (name "unconnected-(SV2-Pad16)") (class "Default")
      (node (ref "SV2") (pin "16") (pinfunction "16_16") (pintype "passive"))
    )
    (net (code "90") (name "unconnected-(U2-CBUS2-Pad13)") (class "Default")
      (node (ref "U2") (pin "13") (pinfunction "CBUS2_13") (pintype "bidirectional"))
    )
    (net (code "91") (name "unconnected-(U2-CBUS3-Pad14)") (class "Default")
      (node (ref "U2") (pin "14") (pinfunction "CBUS3_14") (pintype "bidirectional"))
    )
    (net (code "92") (name "unconnected-(U2-CBUS4-Pad12)") (class "Default")
      (node (ref "U2") (pin "12") (pinfunction "CBUS4_12") (pintype "bidirectional"))
    )
    (net (code "93") (name "unconnected-(U2-CTS#-Pad11)") (class "Default")
      (node (ref "U2") (pin "11") (pinfunction "CTS#_11") (pintype "input"))
    )
    (net (code "94") (name "unconnected-(U2-DCD#-Pad10)") (class "Default")
      (node (ref "U2") (pin "10") (pinfunction "DCD#_10") (pintype "input"))
    )
    (net (code "95") (name "unconnected-(U2-DSR#-Pad9)") (class "Default")
      (node (ref "U2") (pin "9") (pinfunction "DSR#_9") (pintype "input"))
    )
    (net (code "96") (name "unconnected-(U2-DTR#-Pad2)") (class "Default")
      (node (ref "U2") (pin "2") (pinfunction "DTR#_2") (pintype "output"))
    )
    (net (code "97") (name "unconnected-(U2-OSCI-Pad27)") (class "Default")
      (node (ref "U2") (pin "27") (pinfunction "OSCI_27") (pintype "input"))
    )
    (net (code "98") (name "unconnected-(U2-OSCO-Pad28)") (class "Default")
      (node (ref "U2") (pin "28") (pinfunction "OSCO_28") (pintype "output"))
    )
    (net (code "99") (name "unconnected-(U2-RI#-Pad6)") (class "Default")
      (node (ref "U2") (pin "6") (pinfunction "RI#_6") (pintype "input"))
    )
    (net (code "100") (name "unconnected-(U2-RTS#-Pad3)") (class "Default")
      (node (ref "U2") (pin "3") (pinfunction "RTS#_3") (pintype "output"))
    )
  )
)
